# Debugger.net
KiCad netlist of a schematic drawn in Altium Designer
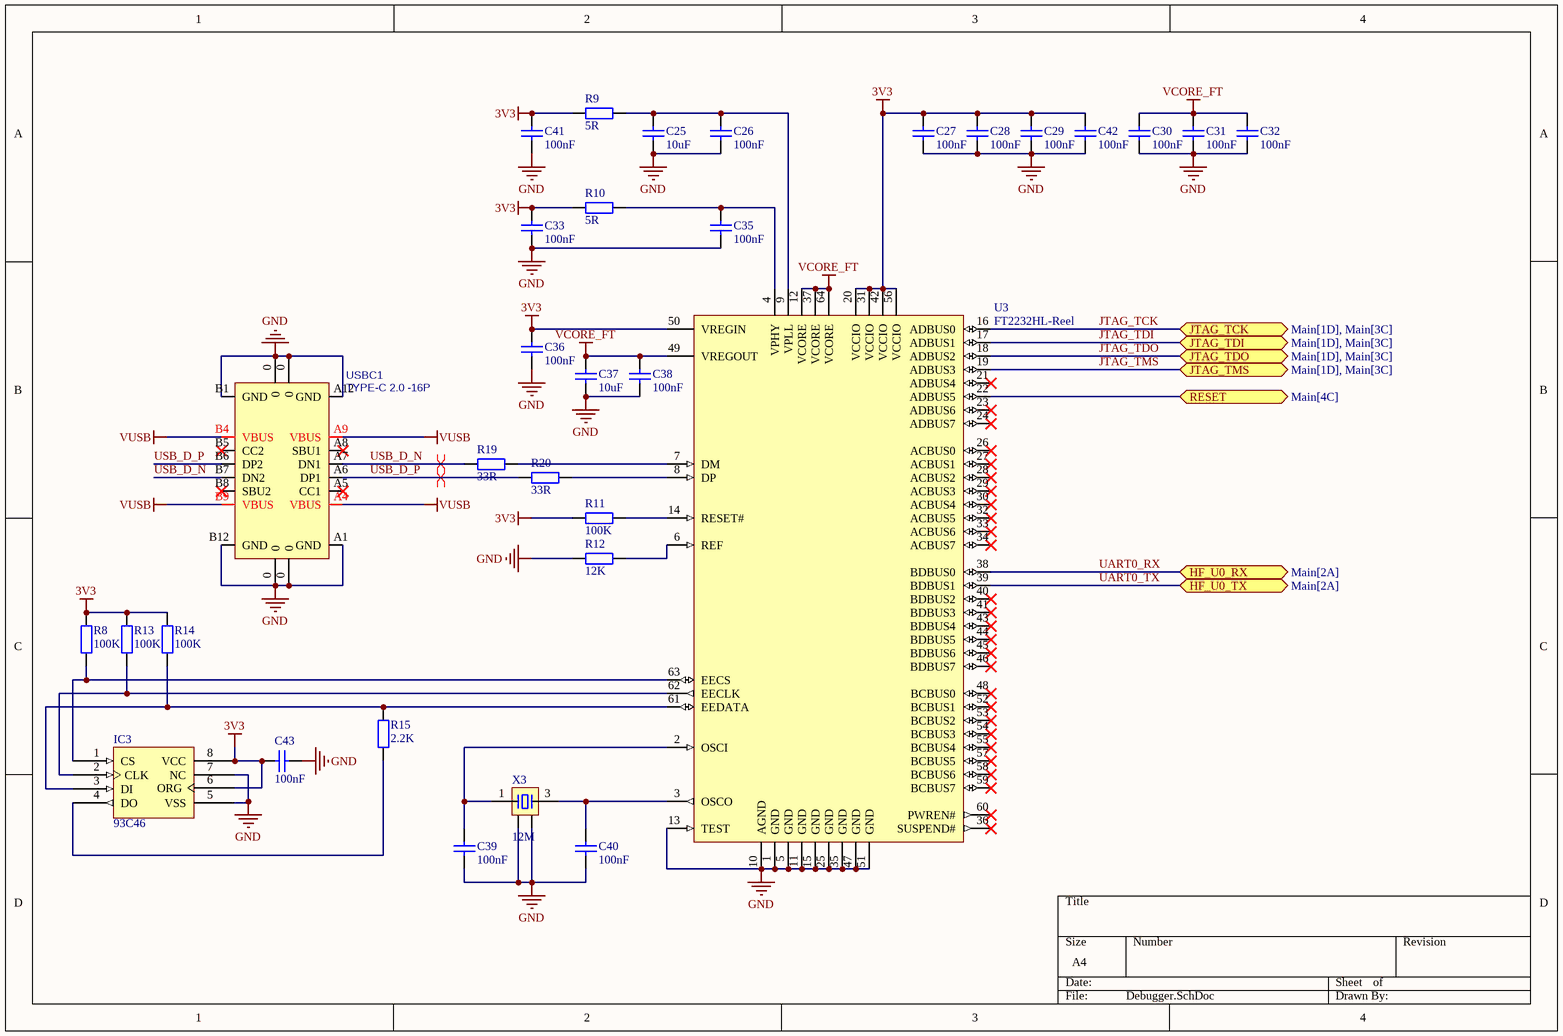
[diagram p0: Debugger.SchDoc]

(export (version "E")
  (design (tool "Eeschema 10.0.6"))
  (components
    (comp (ref "C25")
      (value "10uF")
      (footprint "C0603_NS")
      (description "贴片电容/MLCC电容")
      (libsource (lib "0.1 - 电阻-电容-电感-晶振-晶体-磁珠-电位器-法拉电容-馈通电容") (part "C"))
    )
    (comp (ref "C26")
      (value "100nF")
      (footprint "C0603_NS")
      (description "贴片电容/MLCC电容")
      (libsource (lib "0.1 - 电阻-电容-电感-晶振-晶体-磁珠-电位器-法拉电容-馈通电容") (part "C"))
    )
    (comp (ref "C27")
      (value "100nF")
      (footprint "C0603_NS")
      (description "贴片电容/MLCC电容")
      (libsource (lib "0.1 - 电阻-电容-电感-晶振-晶体-磁珠-电位器-法拉电容-馈通电容") (part "C"))
    )
    (comp (ref "C28")
      (value "100nF")
      (footprint "C0603_NS")
      (description "贴片电容/MLCC电容")
      (libsource (lib "0.1 - 电阻-电容-电感-晶振-晶体-磁珠-电位器-法拉电容-馈通电容") (part "C"))
    )
    (comp (ref "C29")
      (value "100nF")
      (footprint "C0603_NS")
      (description "贴片电容/MLCC电容")
      (libsource (lib "0.1 - 电阻-电容-电感-晶振-晶体-磁珠-电位器-法拉电容-馈通电容") (part "C"))
    )
    (comp (ref "C30")
      (value "100nF")
      (footprint "C0603_NS")
      (description "贴片电容/MLCC电容")
      (libsource (lib "0.1 - 电阻-电容-电感-晶振-晶体-磁珠-电位器-法拉电容-馈通电容") (part "C"))
    )
    (comp (ref "C31")
      (value "100nF")
      (footprint "C0603_NS")
      (description "贴片电容/MLCC电容")
      (libsource (lib "0.1 - 电阻-电容-电感-晶振-晶体-磁珠-电位器-法拉电容-馈通电容") (part "C"))
    )
    (comp (ref "C32")
      (value "100nF")
      (footprint "C0603_NS")
      (description "贴片电容/MLCC电容")
      (libsource (lib "0.1 - 电阻-电容-电感-晶振-晶体-磁珠-电位器-法拉电容-馈通电容") (part "C"))
    )
    (comp (ref "C33")
      (value "100nF")
      (footprint "C0603_NS")
      (description "贴片电容/MLCC电容")
      (libsource (lib "0.1 - 电阻-电容-电感-晶振-晶体-磁珠-电位器-法拉电容-馈通电容") (part "C"))
    )
    (comp (ref "C35")
      (value "100nF")
      (footprint "C0603_NS")
      (description "贴片电容/MLCC电容")
      (libsource (lib "0.1 - 电阻-电容-电感-晶振-晶体-磁珠-电位器-法拉电容-馈通电容") (part "C"))
    )
    (comp (ref "C36")
      (value "100nF")
      (footprint "C0603_NS")
      (description "贴片电容/MLCC电容")
      (libsource (lib "0.1 - 电阻-电容-电感-晶振-晶体-磁珠-电位器-法拉电容-馈通电容") (part "C"))
    )
    (comp (ref "C37")
      (value "10uF")
      (footprint "C0603_NS")
      (description "贴片电容/MLCC电容")
      (libsource (lib "0.1 - 电阻-电容-电感-晶振-晶体-磁珠-电位器-法拉电容-馈通电容") (part "C"))
    )
    (comp (ref "C38")
      (value "100nF")
      (footprint "C0603_NS")
      (description "贴片电容/MLCC电容")
      (libsource (lib "0.1 - 电阻-电容-电感-晶振-晶体-磁珠-电位器-法拉电容-馈通电容") (part "C"))
    )
    (comp (ref "C39")
      (value "100nF")
      (footprint "C0603_NS")
      (description "贴片电容/MLCC电容")
      (libsource (lib "0.1 - 电阻-电容-电感-晶振-晶体-磁珠-电位器-法拉电容-馈通电容") (part "C"))
    )
    (comp (ref "C40")
      (value "100nF")
      (footprint "C0603_NS")
      (description "贴片电容/MLCC电容")
      (libsource (lib "0.1 - 电阻-电容-电感-晶振-晶体-磁珠-电位器-法拉电容-馈通电容") (part "C"))
    )
    (comp (ref "C41")
      (value "100nF")
      (footprint "C0603_NS")
      (description "贴片电容/MLCC电容")
      (libsource (lib "0.1 - 电阻-电容-电感-晶振-晶体-磁珠-电位器-法拉电容-馈通电容") (part "C"))
    )
    (comp (ref "C42")
      (value "100nF")
      (footprint "C0603_NS")
      (description "贴片电容/MLCC电容")
      (libsource (lib "0.1 - 电阻-电容-电感-晶振-晶体-磁珠-电位器-法拉电容-馈通电容") (part "C"))
    )
    (comp (ref "C43")
      (value "100nF")
      (footprint "C0603_NS")
      (description "贴片电容/MLCC电容")
      (libsource (lib "0.1 - 电阻-电容-电感-晶振-晶体-磁珠-电位器-法拉电容-馈通电容") (part "C"))
    )
    (comp (ref "IC3")
      (value "93C46")
      (footprint "SOP8_L")
      (description "外置EEPROM")
      (libsource (lib "0.8 - 常见芯片") (part "93C46"))
    )
    (comp (ref "R8")
      (value "100K")
      (footprint "R0603_NS")
      (description "贴片电阻")
      (libsource (lib "0.1 - 电阻-电容-电感-晶振-晶体-磁珠-电位器-法拉电容-馈通电容") (part "R"))
    )
    (comp (ref "R9")
      (value "5R")
      (footprint "R0603_NS")
      (description "贴片电阻")
      (libsource (lib "0.1 - 电阻-电容-电感-晶振-晶体-磁珠-电位器-法拉电容-馈通电容") (part "R"))
    )
    (comp (ref "R10")
      (value "5R")
      (footprint "R0603_NS")
      (description "贴片电阻")
      (libsource (lib "0.1 - 电阻-电容-电感-晶振-晶体-磁珠-电位器-法拉电容-馈通电容") (part "R"))
    )
    (comp (ref "R11")
      (value "100K")
      (footprint "R0603_NS")
      (description "贴片电阻")
      (libsource (lib "0.1 - 电阻-电容-电感-晶振-晶体-磁珠-电位器-法拉电容-馈通电容") (part "R"))
    )
    (comp (ref "R12")
      (value "12K")
      (footprint "R0603_NS")
      (description "贴片电阻")
      (libsource (lib "0.1 - 电阻-电容-电感-晶振-晶体-磁珠-电位器-法拉电容-馈通电容") (part "R"))
    )
    (comp (ref "R13")
      (value "100K")
      (footprint "R0603_NS")
      (description "贴片电阻")
      (libsource (lib "0.1 - 电阻-电容-电感-晶振-晶体-磁珠-电位器-法拉电容-馈通电容") (part "R"))
    )
    (comp (ref "R14")
      (value "100K")
      (footprint "R0603_NS")
      (description "贴片电阻")
      (libsource (lib "0.1 - 电阻-电容-电感-晶振-晶体-磁珠-电位器-法拉电容-馈通电容") (part "R"))
    )
    (comp (ref "R15")
      (value "2.2K")
      (footprint "R0603_NS")
      (description "贴片电阻")
      (libsource (lib "0.1 - 电阻-电容-电感-晶振-晶体-磁珠-电位器-法拉电容-馈通电容") (part "R"))
    )
    (comp (ref "R19")
      (value "33R")
      (footprint "R0603_NS")
      (description "贴片电阻")
      (libsource (lib "0.1 - 电阻-电容-电感-晶振-晶体-磁珠-电位器-法拉电容-馈通电容") (part "R"))
    )
    (comp (ref "R20")
      (value "33R")
      (footprint "R0603_NS")
      (description "贴片电阻")
      (libsource (lib "0.1 - 电阻-电容-电感-晶振-晶体-磁珠-电位器-法拉电容-馈通电容") (part "R"))
    )
    (comp (ref "U3")
      (value "FT2232HL-Reel")
      (footprint "LQFP-64_M")
      (description "Dual High Speed USB To Multipurpose UART/FIFO IC, 64-pin LQFP, Tape and Reel")
      (fields (field (name "MANUFACTURER") "FTDI"))
      (libsource (lib "Altium Content Vault") (part "COM-UART-FT2232H-LQFP64"))
    )
    (comp (ref "USBC1")
      (value "TYPE-C 2.0 -16P")
      (footprint "USB-C-SMD_16P")
      (description "USB2.0_Type-C_16Pin母座")
      (libsource (lib "0.6 - 电源_RJ45以太网_音频_SD-TF_SIM_ USB Type-C_HDMI插座") (part "USB2.0_Type-C_16Pin"))
    )
    (comp (ref "X3")
      (value "12M")
      (footprint "XTAL-2025-4P")
      (description "4脚无源晶振(谐振器）")
      (libsource (lib "0.1 - 电阻-电容-电感-晶振-晶体-磁珠-电位器-法拉电容-馈通电容") (part "XTAL-4P"))
    )
  )
  (nets
    (net (code "1") (name "/JTAG_TCK") (class "Default")
      (node (ref "U3") (pin "16") (pinfunction "ADBUS0_16") (pintype "bidirectional"))
    )
    (net (code "2") (name "/JTAG_TDI") (class "Default")
      (node (ref "U3") (pin "17") (pinfunction "ADBUS1_17") (pintype "bidirectional"))
    )
    (net (code "3") (name "/JTAG_TDO") (class "Default")
      (node (ref "U3") (pin "18") (pinfunction "ADBUS2_18") (pintype "bidirectional"))
    )
    (net (code "4") (name "/JTAG_TMS") (class "Default")
      (node (ref "U3") (pin "19") (pinfunction "ADBUS3_19") (pintype "bidirectional"))
    )
    (net (code "5") (name "/RESET") (class "Default")
      (node (ref "U3") (pin "22") (pinfunction "ADBUS5_22") (pintype "bidirectional"))
    )
    (net (code "6") (name "/UART0_RX") (class "Default")
      (node (ref "U3") (pin "38") (pinfunction "BDBUS0_38") (pintype "bidirectional"))
    )
    (net (code "7") (name "/UART0_TX") (class "Default")
      (node (ref "U3") (pin "39") (pinfunction "BDBUS1_39") (pintype "bidirectional"))
    )
    (net (code "8") (name "/USB_D_N") (class "Default")
      (node (ref "R19") (pin "2") (pinfunction "2_2") (pintype "passive"))
      (node (ref "USBC1") (pin "A7") (pinfunction "DN1_A7") (pintype "passive"))
      (node (ref "USBC1") (pin "B7") (pinfunction "DN2_B7") (pintype "passive"))
    )
    (net (code "9") (name "/USB_D_P") (class "Default")
      (node (ref "R20") (pin "2") (pinfunction "2_2") (pintype "passive"))
      (node (ref "USBC1") (pin "A6") (pinfunction "DP1_A6") (pintype "passive"))
      (node (ref "USBC1") (pin "B6") (pinfunction "DP2_B6") (pintype "passive"))
    )
    (net (code "10") (name "3V3") (class "Default")
      (node (ref "C27") (pin "2") (pinfunction "2_2") (pintype "passive"))
      (node (ref "C28") (pin "2") (pinfunction "2_2") (pintype "passive"))
      (node (ref "C29") (pin "2") (pinfunction "2_2") (pintype "passive"))
      (node (ref "C33") (pin "2") (pinfunction "2_2") (pintype "passive"))
      (node (ref "C36") (pin "2") (pinfunction "2_2") (pintype "passive"))
      (node (ref "C41") (pin "2") (pinfunction "2_2") (pintype "passive"))
      (node (ref "C42") (pin "2") (pinfunction "2_2") (pintype "passive"))
      (node (ref "C43") (pin "1") (pinfunction "1_1") (pintype "passive"))
      (node (ref "IC3") (pin "6") (pinfunction "ORG_6") (pintype "passive"))
      (node (ref "IC3") (pin "8") (pinfunction "VCC_8") (pintype "power_in"))
      (node (ref "R10") (pin "2") (pinfunction "2_2") (pintype "passive"))
      (node (ref "R11") (pin "2") (pinfunction "2_2") (pintype "passive"))
      (node (ref "R13") (pin "2") (pinfunction "2_2") (pintype "passive"))
      (node (ref "R14") (pin "2") (pinfunction "2_2") (pintype "passive"))
      (node (ref "R8") (pin "2") (pinfunction "2_2") (pintype "passive"))
      (node (ref "R9") (pin "2") (pinfunction "2_2") (pintype "passive"))
      (node (ref "U3") (pin "20") (pinfunction "VCCIO_20") (pintype "power_in"))
      (node (ref "U3") (pin "31") (pinfunction "VCCIO_31") (pintype "power_in"))
      (node (ref "U3") (pin "42") (pinfunction "VCCIO_42") (pintype "power_in"))
      (node (ref "U3") (pin "50") (pinfunction "VREGIN_50") (pintype "power_in"))
      (node (ref "U3") (pin "56") (pinfunction "VCCIO_56") (pintype "power_in"))
    )
    (net (code "11") (name "GND") (class "Default")
      (node (ref "C25") (pin "1") (pinfunction "1_1") (pintype "passive"))
      (node (ref "C26") (pin "1") (pinfunction "1_1") (pintype "passive"))
      (node (ref "C27") (pin "1") (pinfunction "1_1") (pintype "passive"))
      (node (ref "C28") (pin "1") (pinfunction "1_1") (pintype "passive"))
      (node (ref "C29") (pin "1") (pinfunction "1_1") (pintype "passive"))
      (node (ref "C30") (pin "1") (pinfunction "1_1") (pintype "passive"))
      (node (ref "C31") (pin "1") (pinfunction "1_1") (pintype "passive"))
      (node (ref "C32") (pin "1") (pinfunction "1_1") (pintype "passive"))
      (node (ref "C33") (pin "1") (pinfunction "1_1") (pintype "passive"))
      (node (ref "C35") (pin "1") (pinfunction "1_1") (pintype "passive"))
      (node (ref "C36") (pin "1") (pinfunction "1_1") (pintype "passive"))
      (node (ref "C37") (pin "1") (pinfunction "1_1") (pintype "passive"))
      (node (ref "C38") (pin "1") (pinfunction "1_1") (pintype "passive"))
      (node (ref "C39") (pin "1") (pinfunction "1_1") (pintype "passive"))
      (node (ref "C40") (pin "1") (pinfunction "1_1") (pintype "passive"))
      (node (ref "C41") (pin "1") (pinfunction "1_1") (pintype "passive"))
      (node (ref "C42") (pin "1") (pinfunction "1_1") (pintype "passive"))
      (node (ref "C43") (pin "2") (pinfunction "2_2") (pintype "passive"))
      (node (ref "IC3") (pin "5") (pinfunction "VSS_5") (pintype "passive"))
      (node (ref "IC3") (pin "7") (pinfunction "NC_7") (pintype "passive"))
      (node (ref "R12") (pin "1") (pinfunction "1_1") (pintype "passive"))
      (node (ref "U3") (pin "1") (pinfunction "GND_1") (pintype "power_in"))
      (node (ref "U3") (pin "10") (pinfunction "AGND_10") (pintype "power_in"))
      (node (ref "U3") (pin "11") (pinfunction "GND_11") (pintype "power_in"))
      (node (ref "U3") (pin "13") (pinfunction "TEST_13") (pintype "input"))
      (node (ref "U3") (pin "15") (pinfunction "GND_15") (pintype "power_in"))
      (node (ref "U3") (pin "25") (pinfunction "GND_25") (pintype "power_in"))
      (node (ref "U3") (pin "35") (pinfunction "GND_35") (pintype "power_in"))
      (node (ref "U3") (pin "47") (pinfunction "GND_47") (pintype "power_in"))
      (node (ref "U3") (pin "5") (pinfunction "GND_5") (pintype "power_in"))
      (node (ref "U3") (pin "51") (pinfunction "GND_51") (pintype "power_in"))
      (node (ref "USBC1") (pin "0") (pinfunction "0_0") (pintype "passive"))
      (node (ref "USBC1") (pin "A1") (pinfunction "GND_A1") (pintype "passive"))
      (node (ref "USBC1") (pin "A12") (pinfunction "GND_A12") (pintype "passive"))
      (node (ref "USBC1") (pin "B1") (pinfunction "GND_B1") (pintype "passive"))
      (node (ref "USBC1") (pin "B12") (pinfunction "GND_B12") (pintype "passive"))
      (node (ref "X3") (pin "2") (pinfunction "2_2") (pintype "passive"))
      (node (ref "X3") (pin "4") (pinfunction "4_4") (pintype "passive"))
    )
    (net (code "12") (name "Net-(IC3-CLK)") (class "Default")
      (node (ref "IC3") (pin "2") (pinfunction "CLK_2") (pintype "input"))
      (node (ref "R13") (pin "1") (pinfunction "1_1") (pintype "passive"))
      (node (ref "U3") (pin "62") (pinfunction "EECLK_62") (pintype "output"))
    )
    (net (code "13") (name "Net-(IC3-CS)") (class "Default")
      (node (ref "IC3") (pin "1") (pinfunction "CS_1") (pintype "input"))
      (node (ref "R8") (pin "1") (pinfunction "1_1") (pintype "passive"))
      (node (ref "U3") (pin "63") (pinfunction "EECS_63") (pintype "bidirectional"))
    )
    (net (code "14") (name "Net-(IC3-DI)") (class "Default")
      (node (ref "IC3") (pin "3") (pinfunction "DI_3") (pintype "input"))
      (node (ref "R14") (pin "1") (pinfunction "1_1") (pintype "passive"))
      (node (ref "R15") (pin "1") (pinfunction "1_1") (pintype "passive"))
      (node (ref "U3") (pin "61") (pinfunction "EEDATA_61") (pintype "bidirectional"))
    )
    (net (code "15") (name "Net-(IC3-DO)") (class "Default")
      (node (ref "IC3") (pin "4") (pinfunction "DO_4") (pintype "output"))
      (node (ref "R15") (pin "2") (pinfunction "2_2") (pintype "passive"))
    )
    (net (code "16") (name "Net-(U3-DM)") (class "Default")
      (node (ref "R19") (pin "1") (pinfunction "1_1") (pintype "passive"))
      (node (ref "U3") (pin "7") (pinfunction "DM_7") (pintype "input"))
    )
    (net (code "17") (name "Net-(U3-DP)") (class "Default")
      (node (ref "R20") (pin "1") (pinfunction "1_1") (pintype "passive"))
      (node (ref "U3") (pin "8") (pinfunction "DP_8") (pintype "input"))
    )
    (net (code "18") (name "Net-(U3-OSCI)") (class "Default")
      (node (ref "C39") (pin "2") (pinfunction "2_2") (pintype "passive"))
      (node (ref "U3") (pin "2") (pinfunction "OSCI_2") (pintype "input"))
      (node (ref "X3") (pin "1") (pinfunction "1_1") (pintype "passive"))
    )
    (net (code "19") (name "Net-(U3-OSCO)") (class "Default")
      (node (ref "C40") (pin "2") (pinfunction "2_2") (pintype "passive"))
      (node (ref "U3") (pin "3") (pinfunction "OSCO_3") (pintype "output"))
      (node (ref "X3") (pin "3") (pinfunction "3_3") (pintype "passive"))
    )
    (net (code "20") (name "Net-(U3-REF)") (class "Default")
      (node (ref "R12") (pin "2") (pinfunction "2_2") (pintype "passive"))
      (node (ref "U3") (pin "6") (pinfunction "REF_6") (pintype "input"))
    )
    (net (code "21") (name "Net-(U3-RESET#)") (class "Default")
      (node (ref "R11") (pin "1") (pinfunction "1_1") (pintype "passive"))
      (node (ref "U3") (pin "14") (pinfunction "RESET#_14") (pintype "input"))
    )
    (net (code "22") (name "Net-(U3-VPHY)") (class "Default")
      (node (ref "C35") (pin "2") (pinfunction "2_2") (pintype "passive"))
      (node (ref "R10") (pin "1") (pinfunction "1_1") (pintype "passive"))
      (node (ref "U3") (pin "4") (pinfunction "VPHY_4") (pintype "power_in"))
    )
    (net (code "23") (name "Net-(U3-VPLL)") (class "Default")
      (node (ref "C25") (pin "2") (pinfunction "2_2") (pintype "passive"))
      (node (ref "C26") (pin "2") (pinfunction "2_2") (pintype "passive"))
      (node (ref "R9") (pin "1") (pinfunction "1_1") (pintype "passive"))
      (node (ref "U3") (pin "9") (pinfunction "VPLL_9") (pintype "power_in"))
    )
    (net (code "24") (name "VCORE_FT") (class "Default")
      (node (ref "C30") (pin "2") (pinfunction "2_2") (pintype "passive"))
      (node (ref "C31") (pin "2") (pinfunction "2_2") (pintype "passive"))
      (node (ref "C32") (pin "2") (pinfunction "2_2") (pintype "passive"))
      (node (ref "C37") (pin "2") (pinfunction "2_2") (pintype "passive"))
      (node (ref "C38") (pin "2") (pinfunction "2_2") (pintype "passive"))
      (node (ref "U3") (pin "12") (pinfunction "VCORE_12") (pintype "power_in"))
      (node (ref "U3") (pin "37") (pinfunction "VCORE_37") (pintype "power_in"))
      (node (ref "U3") (pin "49") (pinfunction "VREGOUT_49") (pintype "power_in"))
      (node (ref "U3") (pin "64") (pinfunction "VCORE_64") (pintype "power_in"))
    )
    (net (code "25") (name "VUSB") (class "Default")
      (node (ref "USBC1") (pin "A4") (pinfunction "VBUS_A4") (pintype "passive"))
      (node (ref "USBC1") (pin "A9") (pinfunction "VBUS_A9") (pintype "passive"))
      (node (ref "USBC1") (pin "B4") (pinfunction "VBUS_B4") (pintype "passive"))
      (node (ref "USBC1") (pin "B9") (pinfunction "VBUS_B9") (pintype "passive"))
    )
    (net (code "26") (name "unconnected-(U3-ACBUS0-Pad26)") (class "Default")
      (node (ref "U3") (pin "26") (pinfunction "ACBUS0_26") (pintype "bidirectional+no_connect"))
    )
    (net (code "27") (name "unconnected-(U3-ACBUS1-Pad27)") (class "Default")
      (node (ref "U3") (pin "27") (pinfunction "ACBUS1_27") (pintype "bidirectional+no_connect"))
    )
    (net (code "28") (name "unconnected-(U3-ACBUS2-Pad28)") (class "Default")
      (node (ref "U3") (pin "28") (pinfunction "ACBUS2_28") (pintype "bidirectional+no_connect"))
    )
    (net (code "29") (name "unconnected-(U3-ACBUS3-Pad29)") (class "Default")
      (node (ref "U3") (pin "29") (pinfunction "ACBUS3_29") (pintype "bidirectional+no_connect"))
    )
    (net (code "30") (name "unconnected-(U3-ACBUS4-Pad30)") (class "Default")
      (node (ref "U3") (pin "30") (pinfunction "ACBUS4_30") (pintype "bidirectional+no_connect"))
    )
    (net (code "31") (name "unconnected-(U3-ACBUS5-Pad32)") (class "Default")
      (node (ref "U3") (pin "32") (pinfunction "ACBUS5_32") (pintype "bidirectional+no_connect"))
    )
    (net (code "32") (name "unconnected-(U3-ACBUS6-Pad33)") (class "Default")
      (node (ref "U3") (pin "33") (pinfunction "ACBUS6_33") (pintype "bidirectional+no_connect"))
    )
    (net (code "33") (name "unconnected-(U3-ACBUS7-Pad34)") (class "Default")
      (node (ref "U3") (pin "34") (pinfunction "ACBUS7_34") (pintype "bidirectional+no_connect"))
    )
    (net (code "34") (name "unconnected-(U3-ADBUS4-Pad21)") (class "Default")
      (node (ref "U3") (pin "21") (pinfunction "ADBUS4_21") (pintype "bidirectional+no_connect"))
    )
    (net (code "35") (name "unconnected-(U3-ADBUS6-Pad23)") (class "Default")
      (node (ref "U3") (pin "23") (pinfunction "ADBUS6_23") (pintype "bidirectional+no_connect"))
    )
    (net (code "36") (name "unconnected-(U3-ADBUS7-Pad24)") (class "Default")
      (node (ref "U3") (pin "24") (pinfunction "ADBUS7_24") (pintype "bidirectional+no_connect"))
    )
    (net (code "37") (name "unconnected-(U3-BCBUS0-Pad48)") (class "Default")
      (node (ref "U3") (pin "48") (pinfunction "BCBUS0_48") (pintype "bidirectional+no_connect"))
    )
    (net (code "38") (name "unconnected-(U3-BCBUS1-Pad52)") (class "Default")
      (node (ref "U3") (pin "52") (pinfunction "BCBUS1_52") (pintype "bidirectional+no_connect"))
    )
    (net (code "39") (name "unconnected-(U3-BCBUS2-Pad53)") (class "Default")
      (node (ref "U3") (pin "53") (pinfunction "BCBUS2_53") (pintype "bidirectional+no_connect"))
    )
    (net (code "40") (name "unconnected-(U3-BCBUS3-Pad54)") (class "Default")
      (node (ref "U3") (pin "54") (pinfunction "BCBUS3_54") (pintype "bidirectional+no_connect"))
    )
    (net (code "41") (name "unconnected-(U3-BCBUS4-Pad55)") (class "Default")
      (node (ref "U3") (pin "55") (pinfunction "BCBUS4_55") (pintype "bidirectional+no_connect"))
    )
    (net (code "42") (name "unconnected-(U3-BCBUS5-Pad57)") (class "Default")
      (node (ref "U3") (pin "57") (pinfunction "BCBUS5_57") (pintype "bidirectional+no_connect"))
    )
    (net (code "43") (name "unconnected-(U3-BCBUS6-Pad58)") (class "Default")
      (node (ref "U3") (pin "58") (pinfunction "BCBUS6_58") (pintype "bidirectional+no_connect"))
    )
    (net (code "44") (name "unconnected-(U3-BCBUS7-Pad59)") (class "Default")
      (node (ref "U3") (pin "59") (pinfunction "BCBUS7_59") (pintype "bidirectional+no_connect"))
    )
    (net (code "45") (name "unconnected-(U3-BDBUS2-Pad40)") (class "Default")
      (node (ref "U3") (pin "40") (pinfunction "BDBUS2_40") (pintype "bidirectional+no_connect"))
    )
    (net (code "46") (name "unconnected-(U3-BDBUS3-Pad41)") (class "Default")
      (node (ref "U3") (pin "41") (pinfunction "BDBUS3_41") (pintype "bidirectional+no_connect"))
    )
    (net (code "47") (name "unconnected-(U3-BDBUS4-Pad43)") (class "Default")
      (node (ref "U3") (pin "43") (pinfunction "BDBUS4_43") (pintype "bidirectional+no_connect"))
    )
    (net (code "48") (name "unconnected-(U3-BDBUS5-Pad44)") (class "Default")
      (node (ref "U3") (pin "44") (pinfunction "BDBUS5_44") (pintype "bidirectional+no_connect"))
    )
    (net (code "49") (name "unconnected-(U3-BDBUS6-Pad45)") (class "Default")
      (node (ref "U3") (pin "45") (pinfunction "BDBUS6_45") (pintype "bidirectional+no_connect"))
    )
    (net (code "50") (name "unconnected-(U3-BDBUS7-Pad46)") (class "Default")
      (node (ref "U3") (pin "46") (pinfunction "BDBUS7_46") (pintype "bidirectional+no_connect"))
    )
    (net (code "51") (name "unconnected-(U3-PWREN#-Pad60)") (class "Default")
      (node (ref "U3") (pin "60") (pinfunction "PWREN#_60") (pintype "output+no_connect"))
    )
    (net (code "52") (name "unconnected-(U3-SUSPEND#-Pad36)") (class "Default")
      (node (ref "U3") (pin "36") (pinfunction "SUSPEND#_36") (pintype "output+no_connect"))
    )
    (net (code "53") (name "unconnected-(USBC1-CC1-PadA5)") (class "Default")
      (node (ref "USBC1") (pin "A5") (pinfunction "CC1_A5") (pintype "passive+no_connect"))
    )
    (net (code "54") (name "unconnected-(USBC1-CC2-PadB5)") (class "Default")
      (node (ref "USBC1") (pin "B5") (pinfunction "CC2_B5") (pintype "passive+no_connect"))
    )
    (net (code "55") (name "unconnected-(USBC1-SBU1-PadA8)") (class "Default")
      (node (ref "USBC1") (pin "A8") (pinfunction "SBU1_A8") (pintype "passive+no_connect"))
    )
    (net (code "56") (name "unconnected-(USBC1-SBU2-PadB8)") (class "Default")
      (node (ref "USBC1") (pin "B8") (pinfunction "SBU2_B8") (pintype "passive+no_connect"))
    )
  )
)
